# 1.net
KiCad netlist of a schematic drawn in EAGLE
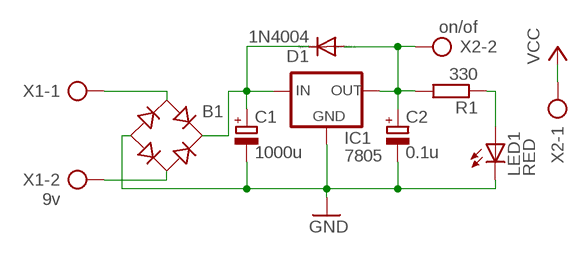
[diagram p0: schematic, sheet 1]
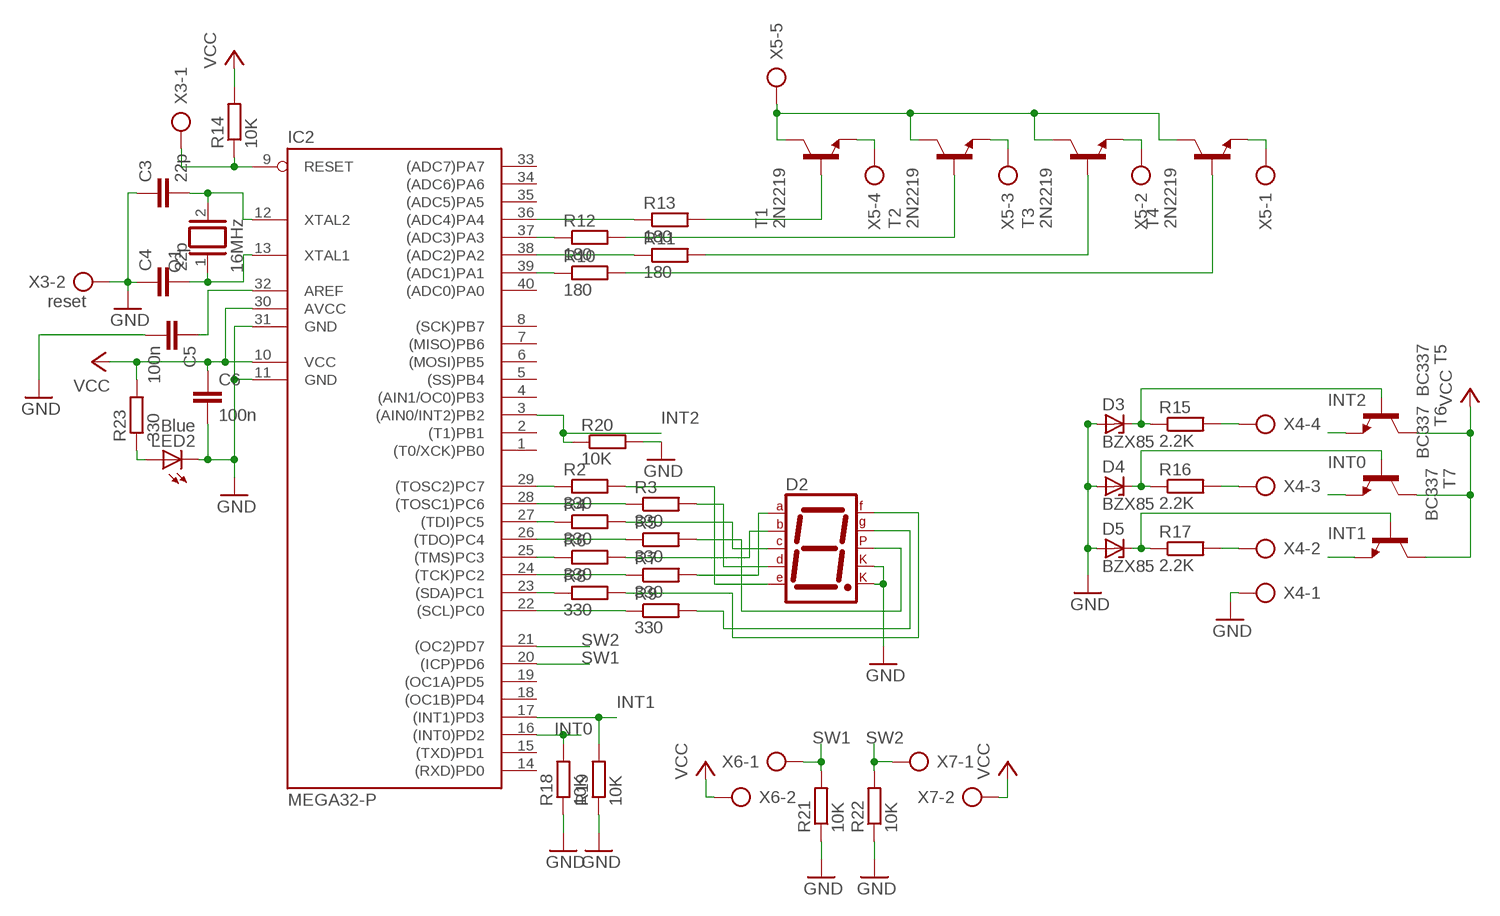
[diagram p1: schematic, sheet 2]

(export (version "E")
  (design (tool "Eeschema 10.0.6"))
  (components
    (comp (ref "B1")
      (value "RB1A")
      (footprint "eagle-import:RB1A")
      (libsource (lib "eagle-import") (part "RB1A"))
    )
    (comp (ref "C1")
      (value "1000u")
      (footprint "eagle-import:E3,5-8")
      (libsource (lib "eagle-import") (part "CPOL-EUE3.5-8"))
    )
    (comp (ref "C2")
      (value "0.1u")
      (footprint "eagle-import:E2-5")
      (libsource (lib "eagle-import") (part "CPOL-EUE2-5"))
    )
    (comp (ref "D1")
      (value "1N4004")
      (footprint "eagle-import:DO41-10")
      (libsource (lib "eagle-import") (part "1N4004"))
    )
    (comp (ref "IC1")
      (value "7805")
      (footprint "eagle-import:78XXS")
      (libsource (lib "eagle-import") (part "78XXS"))
    )
    (comp (ref "LED1")
      (value "RED")
      (footprint "eagle-import:LED5MM")
      (libsource (lib "eagle-import") (part "LED5MM"))
    )
    (comp (ref "R1")
      (value "330")
      (footprint "eagle-import:0204_7")
      (libsource (lib "eagle-import") (part "R-EU_0204/7"))
    )
    (comp (ref "X1")
      (value "9v")
      (footprint "eagle-import:AK500_2")
      (libsource (lib "eagle-import") (part "AK500/2"))
    )
    (comp (ref "X2")
      (value "on/of")
      (footprint "eagle-import:AK500_2")
      (libsource (lib "eagle-import") (part "AK500/2"))
    )
    (comp (ref "C3")
      (value "22p")
      (footprint "eagle-import:C025-024X044")
      (libsource (lib "eagle-import") (part "C-EU025-024X044"))
    )
    (comp (ref "C4")
      (value "22p")
      (footprint "eagle-import:C025-024X044")
      (libsource (lib "eagle-import") (part "C-EU025-024X044"))
    )
    (comp (ref "C5")
      (value "100n")
      (footprint "eagle-import:C025-024X044")
      (libsource (lib "eagle-import") (part "C-EU025-024X044"))
    )
    (comp (ref "C6")
      (value "100n")
      (footprint "eagle-import:C025-024X044")
      (libsource (lib "eagle-import") (part "C-EU025-024X044"))
    )
    (comp (ref "D2")
      (value "7SEG-CK")
      (footprint "eagle-import:7SEG-13")
      (libsource (lib "eagle-import") (part "7SEG-CK"))
    )
    (comp (ref "D3")
      (value "BZX85")
      (footprint "eagle-import:DO41Z10")
      (libsource (lib "eagle-import") (part "BZX85"))
    )
    (comp (ref "D4")
      (value "BZX85")
      (footprint "eagle-import:DO41Z10")
      (libsource (lib "eagle-import") (part "BZX85"))
    )
    (comp (ref "D5")
      (value "BZX85")
      (footprint "eagle-import:DO41Z10")
      (libsource (lib "eagle-import") (part "BZX85"))
    )
    (comp (ref "IC2")
      (value "MEGA32-P")
      (footprint "eagle-import:DIL40")
      (fields (field (name "MPN") "ATMEGA32-16PU"))
      (libsource (lib "eagle-import") (part "MEGA32-P"))
    )
    (comp (ref "LED2")
      (value "Blue")
      (footprint "eagle-import:LED5MM")
      (libsource (lib "eagle-import") (part "LED5MM"))
    )
    (comp (ref "Q1")
      (value "16MHz")
      (footprint "eagle-import:Q")
      (libsource (lib "eagle-import") (part "XTAL"))
    )
    (comp (ref "R2")
      (value "330")
      (footprint "eagle-import:0204_7")
      (libsource (lib "eagle-import") (part "R-EU_0204/7"))
    )
    (comp (ref "R3")
      (value "330")
      (footprint "eagle-import:0204_7")
      (libsource (lib "eagle-import") (part "R-EU_0204/7"))
    )
    (comp (ref "R4")
      (value "330")
      (footprint "eagle-import:0204_7")
      (libsource (lib "eagle-import") (part "R-EU_0204/7"))
    )
    (comp (ref "R5")
      (value "330")
      (footprint "eagle-import:0204_7")
      (libsource (lib "eagle-import") (part "R-EU_0204/7"))
    )
    (comp (ref "R6")
      (value "330")
      (footprint "eagle-import:0204_7")
      (libsource (lib "eagle-import") (part "R-EU_0204/7"))
    )
    (comp (ref "R7")
      (value "330")
      (footprint "eagle-import:0204_7")
      (libsource (lib "eagle-import") (part "R-EU_0204/7"))
    )
    (comp (ref "R8")
      (value "330")
      (footprint "eagle-import:0204_7")
      (libsource (lib "eagle-import") (part "R-EU_0204/7"))
    )
    (comp (ref "R9")
      (value "330")
      (footprint "eagle-import:0204_7")
      (libsource (lib "eagle-import") (part "R-EU_0204/7"))
    )
    (comp (ref "R10")
      (value "180")
      (footprint "eagle-import:0204_7")
      (libsource (lib "eagle-import") (part "R-EU_0204/7"))
    )
    (comp (ref "R11")
      (value "180")
      (footprint "eagle-import:0204_7")
      (libsource (lib "eagle-import") (part "R-EU_0204/7"))
    )
    (comp (ref "R12")
      (value "180")
      (footprint "eagle-import:0204_7")
      (libsource (lib "eagle-import") (part "R-EU_0204/7"))
    )
    (comp (ref "R13")
      (value "180")
      (footprint "eagle-import:0204_7")
      (libsource (lib "eagle-import") (part "R-EU_0204/7"))
    )
    (comp (ref "R14")
      (value "10K")
      (footprint "eagle-import:0204_7")
      (libsource (lib "eagle-import") (part "R-EU_0204/7"))
    )
    (comp (ref "R15")
      (value "2.2K")
      (footprint "eagle-import:0207_10")
      (libsource (lib "eagle-import") (part "R-EU_0207/10"))
    )
    (comp (ref "R16")
      (value "2.2K")
      (footprint "eagle-import:0207_10")
      (libsource (lib "eagle-import") (part "R-EU_0207/10"))
    )
    (comp (ref "R17")
      (value "2.2K")
      (footprint "eagle-import:0207_10")
      (libsource (lib "eagle-import") (part "R-EU_0207/10"))
    )
    (comp (ref "R18")
      (value "10K")
      (footprint "eagle-import:0204_7")
      (libsource (lib "eagle-import") (part "R-EU_0204/7"))
    )
    (comp (ref "R19")
      (value "10K")
      (footprint "eagle-import:0204_7")
      (libsource (lib "eagle-import") (part "R-EU_0204/7"))
    )
    (comp (ref "R20")
      (value "10K")
      (footprint "eagle-import:0204_7")
      (libsource (lib "eagle-import") (part "R-EU_0204/7"))
    )
    (comp (ref "R21")
      (value "10K")
      (footprint "eagle-import:0204_7")
      (libsource (lib "eagle-import") (part "R-EU_0204/7"))
    )
    (comp (ref "R22")
      (value "10K")
      (footprint "eagle-import:0204_7")
      (libsource (lib "eagle-import") (part "R-EU_0204/7"))
    )
    (comp (ref "R23")
      (value "330")
      (footprint "eagle-import:0204_7")
      (libsource (lib "eagle-import") (part "R-EU_0204/7"))
    )
    (comp (ref "T1")
      (value "2N2219")
      (footprint "eagle-import:TO5")
      (libsource (lib "eagle-import") (part "2N2219"))
    )
    (comp (ref "T2")
      (value "2N2219")
      (footprint "eagle-import:TO5")
      (libsource (lib "eagle-import") (part "2N2219"))
    )
    (comp (ref "T3")
      (value "2N2219")
      (footprint "eagle-import:TO5")
      (libsource (lib "eagle-import") (part "2N2219"))
    )
    (comp (ref "T4")
      (value "2N2219")
      (footprint "eagle-import:TO5")
      (libsource (lib "eagle-import") (part "2N2219"))
    )
    (comp (ref "T5")
      (value "BC337")
      (footprint "eagle-import:TO92")
      (libsource (lib "eagle-import") (part "BC337"))
    )
    (comp (ref "T6")
      (value "BC337")
      (footprint "eagle-import:TO92")
      (libsource (lib "eagle-import") (part "BC337"))
    )
    (comp (ref "T7")
      (value "BC337")
      (footprint "eagle-import:TO92")
      (libsource (lib "eagle-import") (part "BC337"))
    )
    (comp (ref "X3")
      (value "reset")
      (footprint "eagle-import:AK500_2")
      (libsource (lib "eagle-import") (part "AK500/2"))
    )
    (comp (ref "X4")
      (value "AK500/4")
      (footprint "eagle-import:AK500_4")
      (libsource (lib "eagle-import") (part "AK500/4"))
    )
    (comp (ref "X5")
      (value "AK500/5")
      (footprint "eagle-import:AK500_5")
      (libsource (lib "eagle-import") (part "AK500/5"))
    )
    (comp (ref "X6")
      (value "AK500/2")
      (footprint "eagle-import:AK500_2")
      (libsource (lib "eagle-import") (part "AK500/2"))
    )
    (comp (ref "X7")
      (value "AK500/2")
      (footprint "eagle-import:AK500_2")
      (libsource (lib "eagle-import") (part "AK500/2"))
    )
  )
  (nets
    (net (code "1") (name "GND") (class "Default")
      (node (ref "B1") (pin "-") (pinfunction "-_-") (pintype "passive"))
      (node (ref "C1") (pin "-") (pinfunction "-_-") (pintype "passive"))
      (node (ref "C2") (pin "-") (pinfunction "-_-") (pintype "passive"))
      (node (ref "C3") (pin "1") (pinfunction "1_1") (pintype "passive"))
      (node (ref "C4") (pin "1") (pinfunction "1_1") (pintype "passive"))
      (node (ref "C5") (pin "2") (pinfunction "2_2") (pintype "passive"))
      (node (ref "C6") (pin "2") (pinfunction "2_2") (pintype "passive"))
      (node (ref "D2") (pin "3") (pinfunction "CK1_3") (pintype "passive"))
      (node (ref "D2") (pin "8") (pinfunction "CK2_8") (pintype "passive"))
      (node (ref "D3") (pin "A") (pinfunction "A_A") (pintype "passive"))
      (node (ref "D4") (pin "A") (pinfunction "A_A") (pintype "passive"))
      (node (ref "D5") (pin "A") (pinfunction "A_A") (pintype "passive"))
      (node (ref "IC1") (pin "GND") (pinfunction "GND_GND") (pintype "input"))
      (node (ref "IC2") (pin "11") (pinfunction "GND_11") (pintype "power_in"))
      (node (ref "IC2") (pin "31") (pinfunction "GND_31") (pintype "power_in"))
      (node (ref "LED1") (pin "K") (pinfunction "C_K") (pintype "passive"))
      (node (ref "LED2") (pin "K") (pinfunction "C_K") (pintype "passive"))
      (node (ref "R18") (pin "1") (pinfunction "1_1") (pintype "passive"))
      (node (ref "R19") (pin "1") (pinfunction "1_1") (pintype "passive"))
      (node (ref "R20") (pin "2") (pinfunction "2_2") (pintype "passive"))
      (node (ref "R21") (pin "1") (pinfunction "1_1") (pintype "passive"))
      (node (ref "R22") (pin "1") (pinfunction "1_1") (pintype "passive"))
      (node (ref "X3") (pin "2") (pinfunction "KL_2") (pintype "passive"))
      (node (ref "X4") (pin "1") (pinfunction "KL_1") (pintype "passive"))
    )
    (net (code "2") (name "INT0") (class "Default")
      (node (ref "IC2") (pin "16") (pinfunction "(INT0)PD2_16") (pintype "bidirectional"))
      (node (ref "R18") (pin "2") (pinfunction "2_2") (pintype "passive"))
      (node (ref "T6") (pin "1") (pinfunction "E_1") (pintype "passive"))
    )
    (net (code "3") (name "INT1") (class "Default")
      (node (ref "IC2") (pin "17") (pinfunction "(INT1)PD3_17") (pintype "bidirectional"))
      (node (ref "R19") (pin "2") (pinfunction "2_2") (pintype "passive"))
      (node (ref "T7") (pin "1") (pinfunction "E_1") (pintype "passive"))
    )
    (net (code "4") (name "INT2") (class "Default")
      (node (ref "IC2") (pin "3") (pinfunction "(AIN0/INT2)PB2_3") (pintype "bidirectional"))
      (node (ref "R20") (pin "1") (pinfunction "1_1") (pintype "passive"))
      (node (ref "T5") (pin "1") (pinfunction "E_1") (pintype "passive"))
    )
    (net (code "5") (name "Net-(B1-Pad+)") (class "Default")
      (node (ref "B1") (pin "+") (pinfunction "+_+") (pintype "passive"))
      (node (ref "C1") (pin "+") (pinfunction "+_+") (pintype "passive"))
      (node (ref "D1") (pin "C") (pinfunction "C_C") (pintype "passive"))
      (node (ref "IC1") (pin "IN") (pinfunction "IN_IN") (pintype "input"))
    )
    (net (code "6") (name "Net-(D2-A)") (class "Default")
      (node (ref "D2") (pin "7") (pinfunction "A_7") (pintype "passive"))
      (node (ref "R7") (pin "2") (pinfunction "2_2") (pintype "passive"))
    )
    (net (code "7") (name "Net-(D2-B)") (class "Default")
      (node (ref "D2") (pin "6") (pinfunction "B_6") (pintype "passive"))
      (node (ref "R6") (pin "2") (pinfunction "2_2") (pintype "passive"))
    )
    (net (code "8") (name "Net-(D2-C)") (class "Default")
      (node (ref "D2") (pin "4") (pinfunction "C_4") (pintype "passive"))
      (node (ref "R4") (pin "2") (pinfunction "2_2") (pintype "passive"))
    )
    (net (code "9") (name "Net-(D2-D)") (class "Default")
      (node (ref "D2") (pin "2") (pinfunction "D_2") (pintype "passive"))
      (node (ref "R3") (pin "2") (pinfunction "2_2") (pintype "passive"))
    )
    (net (code "10") (name "Net-(D2-DP)") (class "Default")
      (node (ref "D2") (pin "5") (pinfunction "DP_5") (pintype "passive"))
      (node (ref "R5") (pin "2") (pinfunction "2_2") (pintype "passive"))
    )
    (net (code "11") (name "Net-(D2-E)") (class "Default")
      (node (ref "D2") (pin "1") (pinfunction "E_1") (pintype "passive"))
      (node (ref "R2") (pin "2") (pinfunction "2_2") (pintype "passive"))
    )
    (net (code "12") (name "Net-(D2-F)") (class "Default")
      (node (ref "D2") (pin "9") (pinfunction "F_9") (pintype "passive"))
      (node (ref "R8") (pin "2") (pinfunction "2_2") (pintype "passive"))
    )
    (net (code "13") (name "Net-(D2-G)") (class "Default")
      (node (ref "D2") (pin "10") (pinfunction "G_10") (pintype "passive"))
      (node (ref "R9") (pin "2") (pinfunction "2_2") (pintype "passive"))
    )
    (net (code "14") (name "Net-(IC2-(ADC1)PA1)") (class "Default")
      (node (ref "IC2") (pin "39") (pinfunction "(ADC1)PA1_39") (pintype "bidirectional"))
      (node (ref "R10") (pin "1") (pinfunction "1_1") (pintype "passive"))
    )
    (net (code "15") (name "Net-(IC2-(ADC2)PA2)") (class "Default")
      (node (ref "IC2") (pin "38") (pinfunction "(ADC2)PA2_38") (pintype "bidirectional"))
      (node (ref "R11") (pin "1") (pinfunction "1_1") (pintype "passive"))
    )
    (net (code "16") (name "Net-(IC2-(ADC3)PA3)") (class "Default")
      (node (ref "IC2") (pin "37") (pinfunction "(ADC3)PA3_37") (pintype "bidirectional"))
      (node (ref "R12") (pin "1") (pinfunction "1_1") (pintype "passive"))
    )
    (net (code "17") (name "Net-(IC2-(ADC4)PA4)") (class "Default")
      (node (ref "IC2") (pin "36") (pinfunction "(ADC4)PA4_36") (pintype "bidirectional"))
      (node (ref "R13") (pin "1") (pinfunction "1_1") (pintype "passive"))
    )
    (net (code "18") (name "Net-(IC2-(SCL)PC0)") (class "Default")
      (node (ref "IC2") (pin "22") (pinfunction "(SCL)PC0_22") (pintype "bidirectional"))
      (node (ref "R9") (pin "1") (pinfunction "1_1") (pintype "passive"))
    )
    (net (code "19") (name "Net-(IC2-(SDA)PC1)") (class "Default")
      (node (ref "IC2") (pin "23") (pinfunction "(SDA)PC1_23") (pintype "bidirectional"))
      (node (ref "R8") (pin "1") (pinfunction "1_1") (pintype "passive"))
    )
    (net (code "20") (name "Net-(IC2-(TCK)PC2)") (class "Default")
      (node (ref "IC2") (pin "24") (pinfunction "(TCK)PC2_24") (pintype "bidirectional"))
      (node (ref "R7") (pin "1") (pinfunction "1_1") (pintype "passive"))
    )
    (net (code "21") (name "Net-(IC2-(TDI)PC5)") (class "Default")
      (node (ref "IC2") (pin "27") (pinfunction "(TDI)PC5_27") (pintype "bidirectional"))
      (node (ref "R4") (pin "1") (pinfunction "1_1") (pintype "passive"))
    )
    (net (code "22") (name "Net-(IC2-(TDO)PC4)") (class "Default")
      (node (ref "IC2") (pin "26") (pinfunction "(TDO)PC4_26") (pintype "bidirectional"))
      (node (ref "R5") (pin "1") (pinfunction "1_1") (pintype "passive"))
    )
    (net (code "23") (name "Net-(IC2-(TMS)PC3)") (class "Default")
      (node (ref "IC2") (pin "25") (pinfunction "(TMS)PC3_25") (pintype "bidirectional"))
      (node (ref "R6") (pin "1") (pinfunction "1_1") (pintype "passive"))
    )
    (net (code "24") (name "Net-(IC2-(TOSC1)PC6)") (class "Default")
      (node (ref "IC2") (pin "28") (pinfunction "(TOSC1)PC6_28") (pintype "bidirectional"))
      (node (ref "R3") (pin "1") (pinfunction "1_1") (pintype "passive"))
    )
    (net (code "25") (name "Net-(IC2-(TOSC2)PC7)") (class "Default")
      (node (ref "IC2") (pin "29") (pinfunction "(TOSC2)PC7_29") (pintype "bidirectional"))
      (node (ref "R2") (pin "1") (pinfunction "1_1") (pintype "passive"))
    )
    (net (code "26") (name "Net-(IC2-AREF)") (class "Default")
      (node (ref "C5") (pin "1") (pinfunction "1_1") (pintype "passive"))
      (node (ref "IC2") (pin "32") (pinfunction "AREF_32") (pintype "passive"))
    )
    (net (code "27") (name "Net-(IC2-RESET)") (class "Default")
      (node (ref "IC2") (pin "9") (pinfunction "RESET_9") (pintype "input"))
      (node (ref "R14") (pin "1") (pinfunction "1_1") (pintype "passive"))
      (node (ref "X3") (pin "1") (pinfunction "KL_1") (pintype "passive"))
    )
    (net (code "28") (name "Net-(IC2-XTAL1)") (class "Default")
      (node (ref "C4") (pin "2") (pinfunction "2_2") (pintype "passive"))
      (node (ref "IC2") (pin "13") (pinfunction "XTAL1_13") (pintype "bidirectional"))
      (node (ref "Q1") (pin "1") (pinfunction "1_1") (pintype "passive"))
    )
    (net (code "29") (name "Net-(IC2-XTAL2)") (class "Default")
      (node (ref "C3") (pin "2") (pinfunction "2_2") (pintype "passive"))
      (node (ref "IC2") (pin "12") (pinfunction "XTAL2_12") (pintype "bidirectional"))
      (node (ref "Q1") (pin "2") (pinfunction "2_2") (pintype "passive"))
    )
    (net (code "30") (name "Net-(LED1-PadA)") (class "Default")
      (node (ref "LED1") (pin "A") (pinfunction "A_A") (pintype "passive"))
      (node (ref "R1") (pin "1") (pinfunction "1_1") (pintype "passive"))
    )
    (net (code "31") (name "Net-(LED2-PadA)") (class "Default")
      (node (ref "LED2") (pin "A") (pinfunction "A_A") (pintype "passive"))
      (node (ref "R23") (pin "1") (pinfunction "1_1") (pintype "passive"))
    )
    (net (code "32") (name "Net-(T1-B)") (class "Default")
      (node (ref "R13") (pin "2") (pinfunction "2_2") (pintype "passive"))
      (node (ref "T1") (pin "2") (pinfunction "B_2") (pintype "passive"))
    )
    (net (code "33") (name "Net-(T1-C)") (class "Default")
      (node (ref "T1") (pin "3") (pinfunction "C_3") (pintype "passive"))
      (node (ref "T2") (pin "3") (pinfunction "C_3") (pintype "passive"))
      (node (ref "T3") (pin "3") (pinfunction "C_3") (pintype "passive"))
      (node (ref "T4") (pin "3") (pinfunction "C_3") (pintype "passive"))
      (node (ref "X5") (pin "5") (pinfunction "KL_5") (pintype "passive"))
    )
    (net (code "34") (name "Net-(T1-E)") (class "Default")
      (node (ref "T1") (pin "1") (pinfunction "E_1") (pintype "passive"))
      (node (ref "X5") (pin "4") (pinfunction "KL_4") (pintype "passive"))
    )
    (net (code "35") (name "Net-(T2-B)") (class "Default")
      (node (ref "R12") (pin "2") (pinfunction "2_2") (pintype "passive"))
      (node (ref "T2") (pin "2") (pinfunction "B_2") (pintype "passive"))
    )
    (net (code "36") (name "Net-(T2-E)") (class "Default")
      (node (ref "T2") (pin "1") (pinfunction "E_1") (pintype "passive"))
      (node (ref "X5") (pin "3") (pinfunction "KL_3") (pintype "passive"))
    )
    (net (code "37") (name "Net-(T3-B)") (class "Default")
      (node (ref "R11") (pin "2") (pinfunction "2_2") (pintype "passive"))
      (node (ref "T3") (pin "2") (pinfunction "B_2") (pintype "passive"))
    )
    (net (code "38") (name "Net-(T3-E)") (class "Default")
      (node (ref "T3") (pin "1") (pinfunction "E_1") (pintype "passive"))
      (node (ref "X5") (pin "2") (pinfunction "KL_2") (pintype "passive"))
    )
    (net (code "39") (name "Net-(T4-B)") (class "Default")
      (node (ref "R10") (pin "2") (pinfunction "2_2") (pintype "passive"))
      (node (ref "T4") (pin "2") (pinfunction "B_2") (pintype "passive"))
    )
    (net (code "40") (name "Net-(T4-E)") (class "Default")
      (node (ref "T4") (pin "1") (pinfunction "E_1") (pintype "passive"))
      (node (ref "X5") (pin "1") (pinfunction "KL_1") (pintype "passive"))
    )
    (net (code "41") (name "Net-(T5-B)") (class "Default")
      (node (ref "D3") (pin "C") (pinfunction "C_C") (pintype "passive"))
      (node (ref "R15") (pin "1") (pinfunction "1_1") (pintype "passive"))
      (node (ref "T5") (pin "2") (pinfunction "B_2") (pintype "passive"))
    )
    (net (code "42") (name "Net-(T6-B)") (class "Default")
      (node (ref "D4") (pin "C") (pinfunction "C_C") (pintype "passive"))
      (node (ref "R16") (pin "1") (pinfunction "1_1") (pintype "passive"))
      (node (ref "T6") (pin "2") (pinfunction "B_2") (pintype "passive"))
    )
    (net (code "43") (name "Net-(T7-B)") (class "Default")
      (node (ref "D5") (pin "C") (pinfunction "C_C") (pintype "passive"))
      (node (ref "R17") (pin "1") (pinfunction "1_1") (pintype "passive"))
      (node (ref "T7") (pin "2") (pinfunction "B_2") (pintype "passive"))
    )
    (net (code "44") (name "Net-(X1A-KL)") (class "Default")
      (node (ref "B1") (pin "AC1") (pinfunction "AC1_AC1") (pintype "passive"))
      (node (ref "X1") (pin "1") (pinfunction "KL_1") (pintype "passive"))
    )
    (net (code "45") (name "Net-(X1B-KL)") (class "Default")
      (node (ref "B1") (pin "AC2") (pinfunction "AC2_AC2") (pintype "passive"))
      (node (ref "X1") (pin "2") (pinfunction "KL_2") (pintype "passive"))
    )
    (net (code "46") (name "Net-(X2B-KL)") (class "Default")
      (node (ref "C2") (pin "+") (pinfunction "+_+") (pintype "passive"))
      (node (ref "D1") (pin "A") (pinfunction "A_A") (pintype "passive"))
      (node (ref "IC1") (pin "OUT") (pinfunction "OUT_OUT") (pintype "passive"))
      (node (ref "R1") (pin "2") (pinfunction "2_2") (pintype "passive"))
      (node (ref "X2") (pin "2") (pinfunction "KL_2") (pintype "passive"))
    )
    (net (code "47") (name "Net-(X4B-KL)") (class "Default")
      (node (ref "R17") (pin "2") (pinfunction "2_2") (pintype "passive"))
      (node (ref "X4") (pin "2") (pinfunction "KL_2") (pintype "passive"))
    )
    (net (code "48") (name "Net-(X4C-KL)") (class "Default")
      (node (ref "R16") (pin "2") (pinfunction "2_2") (pintype "passive"))
      (node (ref "X4") (pin "3") (pinfunction "KL_3") (pintype "passive"))
    )
    (net (code "49") (name "Net-(X4D-KL)") (class "Default")
      (node (ref "R15") (pin "2") (pinfunction "2_2") (pintype "passive"))
      (node (ref "X4") (pin "4") (pinfunction "KL_4") (pintype "passive"))
    )
    (net (code "50") (name "SW1") (class "Default")
      (node (ref "IC2") (pin "20") (pinfunction "(ICP)PD6_20") (pintype "bidirectional"))
      (node (ref "R21") (pin "2") (pinfunction "2_2") (pintype "passive"))
      (node (ref "X6") (pin "1") (pinfunction "KL_1") (pintype "passive"))
    )
    (net (code "51") (name "SW2") (class "Default")
      (node (ref "IC2") (pin "21") (pinfunction "(OC2)PD7_21") (pintype "bidirectional"))
      (node (ref "R22") (pin "2") (pinfunction "2_2") (pintype "passive"))
      (node (ref "X7") (pin "1") (pinfunction "KL_1") (pintype "passive"))
    )
    (net (code "52") (name "VCC") (class "Default")
      (node (ref "C6") (pin "1") (pinfunction "1_1") (pintype "passive"))
      (node (ref "IC2") (pin "10") (pinfunction "VCC_10") (pintype "power_in"))
      (node (ref "IC2") (pin "30") (pinfunction "AVCC_30") (pintype "power_in"))
      (node (ref "R14") (pin "2") (pinfunction "2_2") (pintype "passive"))
      (node (ref "R23") (pin "2") (pinfunction "2_2") (pintype "passive"))
      (node (ref "T5") (pin "3") (pinfunction "C_3") (pintype "passive"))
      (node (ref "T6") (pin "3") (pinfunction "C_3") (pintype "passive"))
      (node (ref "T7") (pin "3") (pinfunction "C_3") (pintype "passive"))
      (node (ref "X2") (pin "1") (pinfunction "KL_1") (pintype "passive"))
      (node (ref "X6") (pin "2") (pinfunction "KL_2") (pintype "passive"))
      (node (ref "X7") (pin "2") (pinfunction "KL_2") (pintype "passive"))
    )
    (net (code "53") (name "unconnected-(IC2-(ADC0)PA0-Pad40)") (class "Default")
      (node (ref "IC2") (pin "40") (pinfunction "(ADC0)PA0_40") (pintype "bidirectional"))
    )
    (net (code "54") (name "unconnected-(IC2-(ADC5)PA5-Pad35)") (class "Default")
      (node (ref "IC2") (pin "35") (pinfunction "(ADC5)PA5_35") (pintype "bidirectional"))
    )
    (net (code "55") (name "unconnected-(IC2-(ADC6)PA6-Pad34)") (class "Default")
      (node (ref "IC2") (pin "34") (pinfunction "(ADC6)PA6_34") (pintype "bidirectional"))
    )
    (net (code "56") (name "unconnected-(IC2-(ADC7)PA7-Pad33)") (class "Default")
      (node (ref "IC2") (pin "33") (pinfunction "(ADC7)PA7_33") (pintype "bidirectional"))
    )
    (net (code "57") (name "unconnected-(IC2-(AIN1{slash}OC0)PB3-Pad4)") (class "Default")
      (node (ref "IC2") (pin "4") (pinfunction "(AIN1/OC0)PB3_4") (pintype "bidirectional"))
    )
    (net (code "58") (name "unconnected-(IC2-(MISO)PB6-Pad7)") (class "Default")
      (node (ref "IC2") (pin "7") (pinfunction "(MISO)PB6_7") (pintype "bidirectional"))
    )
    (net (code "59") (name "unconnected-(IC2-(MOSI)PB5-Pad6)") (class "Default")
      (node (ref "IC2") (pin "6") (pinfunction "(MOSI)PB5_6") (pintype "bidirectional"))
    )
    (net (code "60") (name "unconnected-(IC2-(OC1A)PD5-Pad19)") (class "Default")
      (node (ref "IC2") (pin "19") (pinfunction "(OC1A)PD5_19") (pintype "bidirectional"))
    )
    (net (code "61") (name "unconnected-(IC2-(OC1B)PD4-Pad18)") (class "Default")
      (node (ref "IC2") (pin "18") (pinfunction "(OC1B)PD4_18") (pintype "bidirectional"))
    )
    (net (code "62") (name "unconnected-(IC2-(RXD)PD0-Pad14)") (class "Default")
      (node (ref "IC2") (pin "14") (pinfunction "(RXD)PD0_14") (pintype "bidirectional"))
    )
    (net (code "63") (name "unconnected-(IC2-(SCK)PB7-Pad8)") (class "Default")
      (node (ref "IC2") (pin "8") (pinfunction "(SCK)PB7_8") (pintype "bidirectional"))
    )
    (net (code "64") (name "unconnected-(IC2-(SS)PB4-Pad5)") (class "Default")
      (node (ref "IC2") (pin "5") (pinfunction "(SS)PB4_5") (pintype "bidirectional"))
    )
    (net (code "65") (name "unconnected-(IC2-(T0{slash}XCK)PB0-Pad1)") (class "Default")
      (node (ref "IC2") (pin "1") (pinfunction "(T0/XCK)PB0_1") (pintype "bidirectional"))
    )
    (net (code "66") (name "unconnected-(IC2-(T1)PB1-Pad2)") (class "Default")
      (node (ref "IC2") (pin "2") (pinfunction "(T1)PB1_2") (pintype "bidirectional"))
    )
    (net (code "67") (name "unconnected-(IC2-(TXD)PD1-Pad15)") (class "Default")
      (node (ref "IC2") (pin "15") (pinfunction "(TXD)PD1_15") (pintype "bidirectional"))
    )
  )
)
